# Lab2Sol.net
KiCad netlist of a schematic drawn in EAGLE
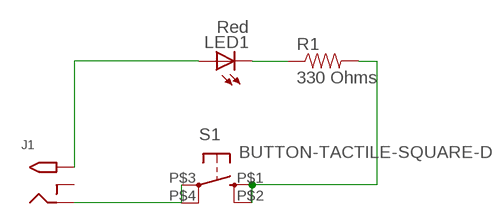
[diagram p0: schematic, sheet 1]

(export (version "E")
  (design (tool "Eeschema 10.0.6"))
  (components
    (comp (ref "J1")
      (value "2.1MMJACKTHM")
      (footprint "eagle-import:PJ-102A")
      (libsource (lib "eagle-import") (part "2.1MMJACKTHM"))
    )
    (comp (ref "LED1")
      (value "Red")
      (footprint "eagle-import:LED5MM")
      (libsource (lib "eagle-import") (part "LED5MM"))
    )
    (comp (ref "R1")
      (value "330 Ohms")
      (footprint "eagle-import:AXIAL-0.3")
      (libsource (lib "eagle-import") (part "RESISTORAXIAL-0.3"))
    )
    (comp (ref "S1")
      (value "BUTTON-TACTILE-SQUARE-DK")
      (footprint "eagle-import:BUTTON-TACTILE-SQUARE-DK")
      (libsource (lib "eagle-import") (part "BUTTON-TACTILE-SQUARE-DK"))
    )
  )
  (nets
    (net (code "1") (name "Net-(J1-PadTIP)") (class "Default")
      (node (ref "J1") (pin "TIP") (pinfunction "TIP_TIP") (pintype "bidirectional"))
      (node (ref "LED1") (pin "A") (pinfunction "A_A") (pintype "passive"))
    )
    (net (code "2") (name "Net-(LED1-C)") (class "Default")
      (node (ref "LED1") (pin "K") (pinfunction "C_K") (pintype "passive"))
      (node (ref "R1") (pin "P$1") (pinfunction "1_P$1") (pintype "passive"))
    )
    (net (code "3") (name "Net-(R1-2)") (class "Default")
      (node (ref "R1") (pin "P$2") (pinfunction "2_P$2") (pintype "passive"))
      (node (ref "S1") (pin "P$1") (pinfunction "S_P$1") (pintype "passive"))
      (node (ref "S1") (pin "P$2") (pinfunction "S1_P$2") (pintype "passive"))
    )
    (net (code "4") (name "Net-(S1-P)") (class "Default")
      (node (ref "J1") (pin "RING") (pinfunction "RING_RING") (pintype "bidirectional"))
      (node (ref "S1") (pin "P$3") (pinfunction "P_P$3") (pintype "passive"))
      (node (ref "S1") (pin "P$4") (pinfunction "P1_P$4") (pintype "passive"))
    )
    (net (code "5") (name "unconnected-(J1-PadRING_SW)") (class "Default")
      (node (ref "J1") (pin "RING_SW") (pinfunction "RING_SW_RING_SW") (pintype "bidirectional"))
    )
  )
)
